# ContactlessIndi.net
KiCad netlist of a schematic drawn in EAGLE
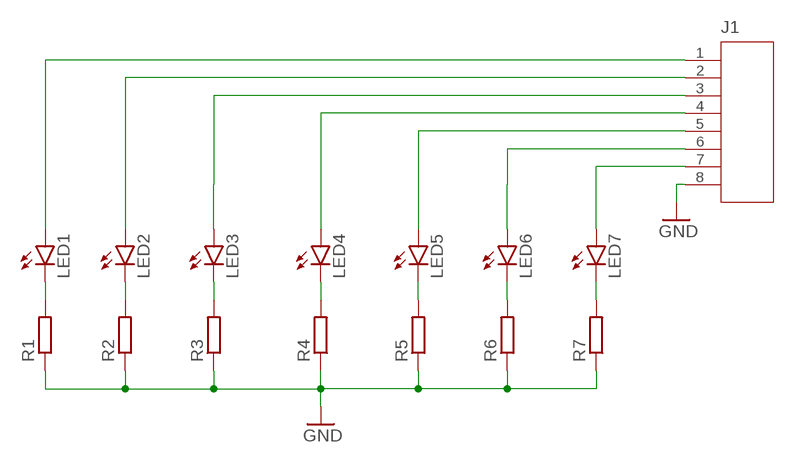
[diagram p0: schematic, sheet 1]

(export (version "E")
  (design (tool "Eeschema 10.0.6"))
  (components
    (comp (ref "J1")
      (value "PINHEADER-818*1")
      (footprint "eagle-import:PINHEADER-8_1")
      (libsource (lib "eagle-import") (part "PINHEADER-8181"))
    )
    (comp (ref "LED1")
      (value "LED5MM")
      (footprint "eagle-import:LED5MM")
      (libsource (lib "eagle-import") (part "LED5MM"))
    )
    (comp (ref "LED2")
      (value "LED5MM")
      (footprint "eagle-import:LED5MM")
      (libsource (lib "eagle-import") (part "LED5MM"))
    )
    (comp (ref "LED3")
      (value "LED5MM")
      (footprint "eagle-import:LED5MM")
      (libsource (lib "eagle-import") (part "LED5MM"))
    )
    (comp (ref "LED4")
      (value "LED5MM")
      (footprint "eagle-import:LED5MM")
      (libsource (lib "eagle-import") (part "LED5MM"))
    )
    (comp (ref "LED5")
      (value "LED5MM")
      (footprint "eagle-import:LED5MM")
      (libsource (lib "eagle-import") (part "LED5MM"))
    )
    (comp (ref "LED6")
      (value "LED5MM")
      (footprint "eagle-import:LED5MM")
      (libsource (lib "eagle-import") (part "LED5MM"))
    )
    (comp (ref "LED7")
      (value "LED5MM")
      (footprint "eagle-import:LED5MM")
      (libsource (lib "eagle-import") (part "LED5MM"))
    )
    (comp (ref "R1")
      (value "R-EU_R1206")
      (footprint "eagle-import:R1206")
      (libsource (lib "eagle-import") (part "R-EU_R1206"))
    )
    (comp (ref "R2")
      (value "R-EU_R1206")
      (footprint "eagle-import:R1206")
      (libsource (lib "eagle-import") (part "R-EU_R1206"))
    )
    (comp (ref "R3")
      (value "R-EU_R1206")
      (footprint "eagle-import:R1206")
      (libsource (lib "eagle-import") (part "R-EU_R1206"))
    )
    (comp (ref "R4")
      (value "R-EU_R1206")
      (footprint "eagle-import:R1206")
      (libsource (lib "eagle-import") (part "R-EU_R1206"))
    )
    (comp (ref "R5")
      (value "R-EU_R1206")
      (footprint "eagle-import:R1206")
      (libsource (lib "eagle-import") (part "R-EU_R1206"))
    )
    (comp (ref "R6")
      (value "R-EU_R1206")
      (footprint "eagle-import:R1206")
      (libsource (lib "eagle-import") (part "R-EU_R1206"))
    )
    (comp (ref "R7")
      (value "R-EU_R1206")
      (footprint "eagle-import:R1206")
      (libsource (lib "eagle-import") (part "R-EU_R1206"))
    )
  )
  (nets
    (net (code "1") (name "GND") (class "Default")
      (node (ref "J1") (pin "8") (pinfunction "8_8") (pintype "bidirectional"))
      (node (ref "R1") (pin "1") (pinfunction "1_1") (pintype "passive"))
      (node (ref "R2") (pin "1") (pinfunction "1_1") (pintype "passive"))
      (node (ref "R3") (pin "1") (pinfunction "1_1") (pintype "passive"))
      (node (ref "R4") (pin "1") (pinfunction "1_1") (pintype "passive"))
      (node (ref "R5") (pin "1") (pinfunction "1_1") (pintype "passive"))
      (node (ref "R6") (pin "1") (pinfunction "1_1") (pintype "passive"))
      (node (ref "R7") (pin "1") (pinfunction "1_1") (pintype "passive"))
    )
    (net (code "2") (name "Net-(J1-Pad1)") (class "Default")
      (node (ref "J1") (pin "1") (pinfunction "1_1") (pintype "bidirectional"))
      (node (ref "LED1") (pin "A") (pinfunction "A_A") (pintype "passive"))
    )
    (net (code "3") (name "Net-(J1-Pad2)") (class "Default")
      (node (ref "J1") (pin "2") (pinfunction "2_2") (pintype "bidirectional"))
      (node (ref "LED2") (pin "A") (pinfunction "A_A") (pintype "passive"))
    )
    (net (code "4") (name "Net-(J1-Pad3)") (class "Default")
      (node (ref "J1") (pin "3") (pinfunction "3_3") (pintype "bidirectional"))
      (node (ref "LED3") (pin "A") (pinfunction "A_A") (pintype "passive"))
    )
    (net (code "5") (name "Net-(J1-Pad4)") (class "Default")
      (node (ref "J1") (pin "4") (pinfunction "4_4") (pintype "bidirectional"))
      (node (ref "LED4") (pin "A") (pinfunction "A_A") (pintype "passive"))
    )
    (net (code "6") (name "Net-(J1-Pad5)") (class "Default")
      (node (ref "J1") (pin "5") (pinfunction "5_5") (pintype "bidirectional"))
      (node (ref "LED5") (pin "A") (pinfunction "A_A") (pintype "passive"))
    )
    (net (code "7") (name "Net-(J1-Pad6)") (class "Default")
      (node (ref "J1") (pin "6") (pinfunction "6_6") (pintype "bidirectional"))
      (node (ref "LED6") (pin "A") (pinfunction "A_A") (pintype "passive"))
    )
    (net (code "8") (name "Net-(J1-Pad7)") (class "Default")
      (node (ref "J1") (pin "7") (pinfunction "7_7") (pintype "bidirectional"))
      (node (ref "LED7") (pin "A") (pinfunction "A_A") (pintype "passive"))
    )
    (net (code "9") (name "Net-(LED1-C)") (class "Default")
      (node (ref "LED1") (pin "K") (pinfunction "C_K") (pintype "passive"))
      (node (ref "R1") (pin "2") (pinfunction "2_2") (pintype "passive"))
    )
    (net (code "10") (name "Net-(LED2-C)") (class "Default")
      (node (ref "LED2") (pin "K") (pinfunction "C_K") (pintype "passive"))
      (node (ref "R2") (pin "2") (pinfunction "2_2") (pintype "passive"))
    )
    (net (code "11") (name "Net-(LED3-C)") (class "Default")
      (node (ref "LED3") (pin "K") (pinfunction "C_K") (pintype "passive"))
      (node (ref "R3") (pin "2") (pinfunction "2_2") (pintype "passive"))
    )
    (net (code "12") (name "Net-(LED4-C)") (class "Default")
      (node (ref "LED4") (pin "K") (pinfunction "C_K") (pintype "passive"))
      (node (ref "R4") (pin "2") (pinfunction "2_2") (pintype "passive"))
    )
    (net (code "13") (name "Net-(LED5-C)") (class "Default")
      (node (ref "LED5") (pin "K") (pinfunction "C_K") (pintype "passive"))
      (node (ref "R5") (pin "2") (pinfunction "2_2") (pintype "passive"))
    )
    (net (code "14") (name "Net-(LED6-C)") (class "Default")
      (node (ref "LED6") (pin "K") (pinfunction "C_K") (pintype "passive"))
      (node (ref "R6") (pin "2") (pinfunction "2_2") (pintype "passive"))
    )
    (net (code "15") (name "Net-(LED7-C)") (class "Default")
      (node (ref "LED7") (pin "K") (pinfunction "C_K") (pintype "passive"))
      (node (ref "R7") (pin "2") (pinfunction "2_2") (pintype "passive"))
    )
  )
)
